# FPGA_MGT.net
KiCad netlist of a schematic drawn in Altium Designer
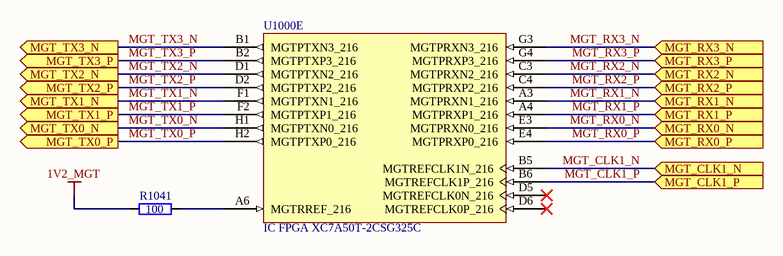
[diagram p0: FPGA_MGT.SchDoc]

(export (version "E")
  (design (tool "Eeschema 10.0.6"))
  (components
    (comp (ref "R1041")
      (value "100")
      (footprint "GEN_R_0402")
      (fields
        (field (name "TOLERANCE") "1%")
        (field (name "MANUFACTURER") "Yageo")
        (field (name "MANUFACTURER PART NUMBER") "RC0402FR-07100RL")
      )
      (libsource (lib "DSO") (part "RES 100 OHM 1% 1/10W 0402"))
    )
    (comp (ref "U1000")
      (value "IC FPGA XC7A50T-2CSG325C")
      (footprint "XILINX_XC7A50T-2CSG325C")
      (description "Artix-7 FPGA, 150 User I/Os, 4 GTP, 324-Ball BGA, Speed Grade 2, Commercial Grade, Pb-Free")
      (fields (field (name "MANUFACTURER") "Xilinx") (field (name "HOUSE PART NUMBER") "XC7A50T-2CSG325C"))
      (libsource (lib "DSO") (part "IC FPGA XC7A50T-2CSG325C"))
    )
  )
  (nets
    (net (code "1") (name "/MGT_CLK1_N") (class "Default")
      (node (ref "U1000") (pin "B5") (pinfunction "MGTREFCLK1N_216_B5") (pintype "input"))
    )
    (net (code "2") (name "/MGT_CLK1_P") (class "Default")
      (node (ref "U1000") (pin "B6") (pinfunction "MGTREFCLK1P_216_B6") (pintype "input"))
    )
    (net (code "3") (name "/MGT_RX0_N") (class "Default")
      (node (ref "U1000") (pin "E3") (pinfunction "MGTPRXN0_216_E3") (pintype "input"))
    )
    (net (code "4") (name "/MGT_RX0_P") (class "Default")
      (node (ref "U1000") (pin "E4") (pinfunction "MGTPRXP0_216_E4") (pintype "input"))
    )
    (net (code "5") (name "/MGT_RX1_N") (class "Default")
      (node (ref "U1000") (pin "A3") (pinfunction "MGTPRXN1_216_A3") (pintype "input"))
    )
    (net (code "6") (name "/MGT_RX1_P") (class "Default")
      (node (ref "U1000") (pin "A4") (pinfunction "MGTPRXP1_216_A4") (pintype "input"))
    )
    (net (code "7") (name "/MGT_RX2_N") (class "Default")
      (node (ref "U1000") (pin "C3") (pinfunction "MGTPRXN2_216_C3") (pintype "input"))
    )
    (net (code "8") (name "/MGT_RX2_P") (class "Default")
      (node (ref "U1000") (pin "C4") (pinfunction "MGTPRXP2_216_C4") (pintype "input"))
    )
    (net (code "9") (name "/MGT_RX3_N") (class "Default")
      (node (ref "U1000") (pin "G3") (pinfunction "MGTPRXN3_216_G3") (pintype "input"))
    )
    (net (code "10") (name "/MGT_RX3_P") (class "Default")
      (node (ref "U1000") (pin "G4") (pinfunction "MGTPRXP3_216_G4") (pintype "input"))
    )
    (net (code "11") (name "/MGT_TX0_N") (class "Default")
      (node (ref "U1000") (pin "H1") (pinfunction "MGTPTXN0_216_H1") (pintype "output"))
    )
    (net (code "12") (name "/MGT_TX0_P") (class "Default")
      (node (ref "U1000") (pin "H2") (pinfunction "MGTPTXP0_216_H2") (pintype "output"))
    )
    (net (code "13") (name "/MGT_TX1_N") (class "Default")
      (node (ref "U1000") (pin "F1") (pinfunction "MGTPTXN1_216_F1") (pintype "output"))
    )
    (net (code "14") (name "/MGT_TX1_P") (class "Default")
      (node (ref "U1000") (pin "F2") (pinfunction "MGTPTXP1_216_F2") (pintype "output"))
    )
    (net (code "15") (name "/MGT_TX2_N") (class "Default")
      (node (ref "U1000") (pin "D1") (pinfunction "MGTPTXN2_216_D1") (pintype "output"))
    )
    (net (code "16") (name "/MGT_TX2_P") (class "Default")
      (node (ref "U1000") (pin "D2") (pinfunction "MGTPTXP2_216_D2") (pintype "output"))
    )
    (net (code "17") (name "/MGT_TX3_N") (class "Default")
      (node (ref "U1000") (pin "B1") (pinfunction "MGTPTXN3_216_B1") (pintype "output"))
    )
    (net (code "18") (name "/MGT_TX3_P") (class "Default")
      (node (ref "U1000") (pin "B2") (pinfunction "MGTPTXP3_216_B2") (pintype "output"))
    )
    (net (code "19") (name "1V2_MGT") (class "Default")
      (node (ref "R1041") (pin "1") (pinfunction "1_1") (pintype "passive"))
    )
    (net (code "20") (name "Net-(U1000E-MGTRREF_216)") (class "Default")
      (node (ref "R1041") (pin "2") (pinfunction "2_2") (pintype "passive"))
      (node (ref "U1000") (pin "A6") (pinfunction "MGTRREF_216_A6") (pintype "input"))
    )
    (net (code "21") (name "unconnected-(U1000E-MGTREFCLK0N_216-PadD5)") (class "Default")
      (node (ref "U1000") (pin "D5") (pinfunction "MGTREFCLK0N_216_D5") (pintype "input+no_connect"))
    )
    (net (code "22") (name "unconnected-(U1000E-MGTREFCLK0P_216-PadD6)") (class "Default")
      (node (ref "U1000") (pin "D6") (pinfunction "MGTREFCLK0P_216_D6") (pintype "input+no_connect"))
    )
  )
)
